# netpwrV0_0.net
KiCad netlist of a schematic drawn in EAGLE
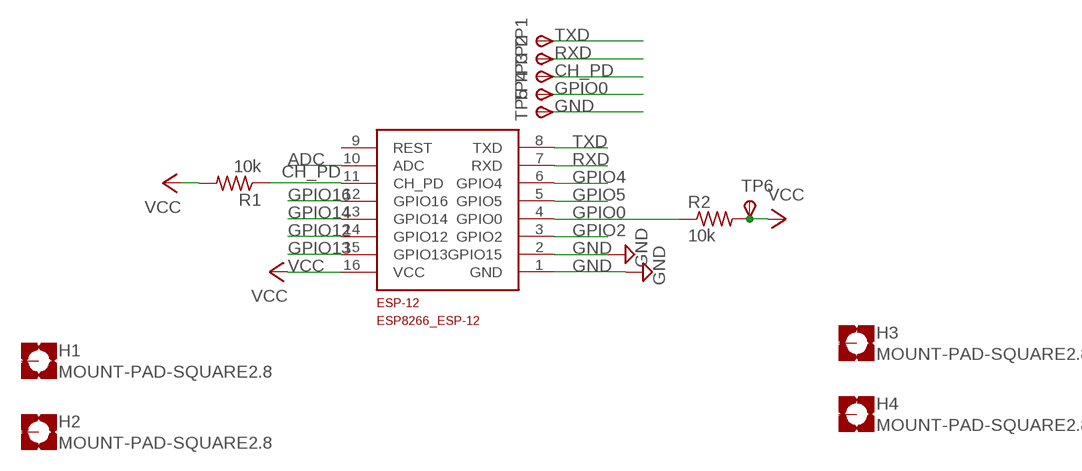
[diagram p0: schematic, sheet 1]

(export (version "E")
  (design (tool "Eeschema 10.0.6"))
  (components
    (comp (ref "ESP-12")
      (value "ESP8266_ESP-12")
      (footprint "eagle-import:ESP8266-ESP12")
      (libsource (lib "eagle-import") (part "ESP8266_ESP-12"))
    )
    (comp (ref "H1")
      (value "MOUNT-PAD-SQUARE2.8")
      (footprint "eagle-import:2,8-PAD-SQUARE")
      (libsource (lib "eagle-import") (part "MOUNT-PAD-SQUARE2.8"))
    )
    (comp (ref "H2")
      (value "MOUNT-PAD-SQUARE2.8")
      (footprint "eagle-import:2,8-PAD-SQUARE")
      (libsource (lib "eagle-import") (part "MOUNT-PAD-SQUARE2.8"))
    )
    (comp (ref "H3")
      (value "MOUNT-PAD-SQUARE2.8")
      (footprint "eagle-import:2,8-PAD-SQUARE")
      (libsource (lib "eagle-import") (part "MOUNT-PAD-SQUARE2.8"))
    )
    (comp (ref "H4")
      (value "MOUNT-PAD-SQUARE2.8")
      (footprint "eagle-import:2,8-PAD-SQUARE")
      (libsource (lib "eagle-import") (part "MOUNT-PAD-SQUARE2.8"))
    )
    (comp (ref "R1")
      (value "10k")
      (footprint "eagle-import:M1206")
      (libsource (lib "eagle-import") (part "R-US_M1206"))
    )
    (comp (ref "R2")
      (value "10k")
      (footprint "eagle-import:M1206")
      (libsource (lib "eagle-import") (part "R-US_M1206"))
    )
    (comp (ref "TP1")
      (value "TPSTP15R")
      (footprint "eagle-import:TP15R")
      (libsource (lib "eagle-import") (part "TPSTP15R"))
    )
    (comp (ref "TP2")
      (value "TPSTP15R")
      (footprint "eagle-import:TP15R")
      (libsource (lib "eagle-import") (part "TPSTP15R"))
    )
    (comp (ref "TP3")
      (value "TPSTP15R")
      (footprint "eagle-import:TP15R")
      (libsource (lib "eagle-import") (part "TPSTP15R"))
    )
    (comp (ref "TP4")
      (value "TPSTP15R")
      (footprint "eagle-import:TP15R")
      (libsource (lib "eagle-import") (part "TPSTP15R"))
    )
    (comp (ref "TP5")
      (value "TPSTP15R")
      (footprint "eagle-import:TP15R")
      (libsource (lib "eagle-import") (part "TPSTP15R"))
    )
    (comp (ref "TP6")
      (value "TPSTP15R")
      (footprint "eagle-import:TP15R")
      (libsource (lib "eagle-import") (part "TPSTP15R"))
    )
  )
  (nets
    (net (code "1") (name "/ADC") (class "Default")
      (node (ref "ESP-12") (pin "10") (pinfunction "ADC_10") (pintype "bidirectional"))
    )
    (net (code "2") (name "/CH_PD") (class "Default")
      (node (ref "ESP-12") (pin "11") (pinfunction "CH_PD_11") (pintype "bidirectional"))
      (node (ref "R1") (pin "1") (pinfunction "1_1") (pintype "passive"))
      (node (ref "TP3") (pin "TP") (pinfunction "PP_TP") (pintype "input"))
    )
    (net (code "3") (name "/GPIO0") (class "Default")
      (node (ref "ESP-12") (pin "4") (pinfunction "GPIO0_4") (pintype "bidirectional"))
      (node (ref "R2") (pin "1") (pinfunction "1_1") (pintype "passive"))
      (node (ref "TP4") (pin "TP") (pinfunction "PP_TP") (pintype "input"))
    )
    (net (code "4") (name "/GPIO2") (class "Default")
      (node (ref "ESP-12") (pin "3") (pinfunction "GPIO2_3") (pintype "bidirectional"))
    )
    (net (code "5") (name "/GPIO4") (class "Default")
      (node (ref "ESP-12") (pin "6") (pinfunction "GPIO4_6") (pintype "bidirectional"))
    )
    (net (code "6") (name "/GPIO5") (class "Default")
      (node (ref "ESP-12") (pin "5") (pinfunction "GPIO5_5") (pintype "bidirectional"))
    )
    (net (code "7") (name "/GPIO12") (class "Default")
      (node (ref "ESP-12") (pin "14") (pinfunction "GPIO12_14") (pintype "bidirectional"))
    )
    (net (code "8") (name "/GPIO13") (class "Default")
      (node (ref "ESP-12") (pin "15") (pinfunction "GPIO13_15") (pintype "bidirectional"))
    )
    (net (code "9") (name "/GPIO14") (class "Default")
      (node (ref "ESP-12") (pin "13") (pinfunction "GPIO14_13") (pintype "bidirectional"))
    )
    (net (code "10") (name "/GPIO16") (class "Default")
      (node (ref "ESP-12") (pin "12") (pinfunction "GPIO16_12") (pintype "bidirectional"))
    )
    (net (code "11") (name "/RXD") (class "Default")
      (node (ref "ESP-12") (pin "7") (pinfunction "RXD_7") (pintype "bidirectional"))
      (node (ref "TP2") (pin "TP") (pinfunction "PP_TP") (pintype "input"))
    )
    (net (code "12") (name "/TXD") (class "Default")
      (node (ref "ESP-12") (pin "8") (pinfunction "TXD_8") (pintype "bidirectional"))
      (node (ref "TP1") (pin "TP") (pinfunction "PP_TP") (pintype "input"))
    )
    (net (code "13") (name "GND") (class "Default")
      (node (ref "ESP-12") (pin "1") (pinfunction "GND_1") (pintype "bidirectional"))
      (node (ref "ESP-12") (pin "2") (pinfunction "GPIO15_2") (pintype "bidirectional"))
      (node (ref "TP5") (pin "TP") (pinfunction "PP_TP") (pintype "input"))
    )
    (net (code "14") (name "VCC") (class "Default")
      (node (ref "ESP-12") (pin "16") (pinfunction "VCC_16") (pintype "bidirectional"))
      (node (ref "R1") (pin "2") (pinfunction "2_2") (pintype "passive"))
      (node (ref "R2") (pin "2") (pinfunction "2_2") (pintype "passive"))
      (node (ref "TP6") (pin "TP") (pinfunction "PP_TP") (pintype "input"))
    )
    (net (code "15") (name "unconnected-(ESP-12-REST-Pad9)") (class "Default")
      (node (ref "ESP-12") (pin "9") (pinfunction "REST_9") (pintype "bidirectional"))
    )
    (net (code "16") (name "unconnected-(H1-MOUNT-PadB2,8)") (class "Default")
      (node (ref "H1") (pin "B2,8") (pinfunction "MOUNT_B2,8") (pintype "passive"))
    )
    (net (code "17") (name "unconnected-(H2-MOUNT-PadB2,8)") (class "Default")
      (node (ref "H2") (pin "B2,8") (pinfunction "MOUNT_B2,8") (pintype "passive"))
    )
    (net (code "18") (name "unconnected-(H3-MOUNT-PadB2,8)") (class "Default")
      (node (ref "H3") (pin "B2,8") (pinfunction "MOUNT_B2,8") (pintype "passive"))
    )
    (net (code "19") (name "unconnected-(H4-MOUNT-PadB2,8)") (class "Default")
      (node (ref "H4") (pin "B2,8") (pinfunction "MOUNT_B2,8") (pintype "passive"))
    )
  )
)
